# 1_P1_schdoc.net
KiCad netlist of a schematic drawn in Altium Designer
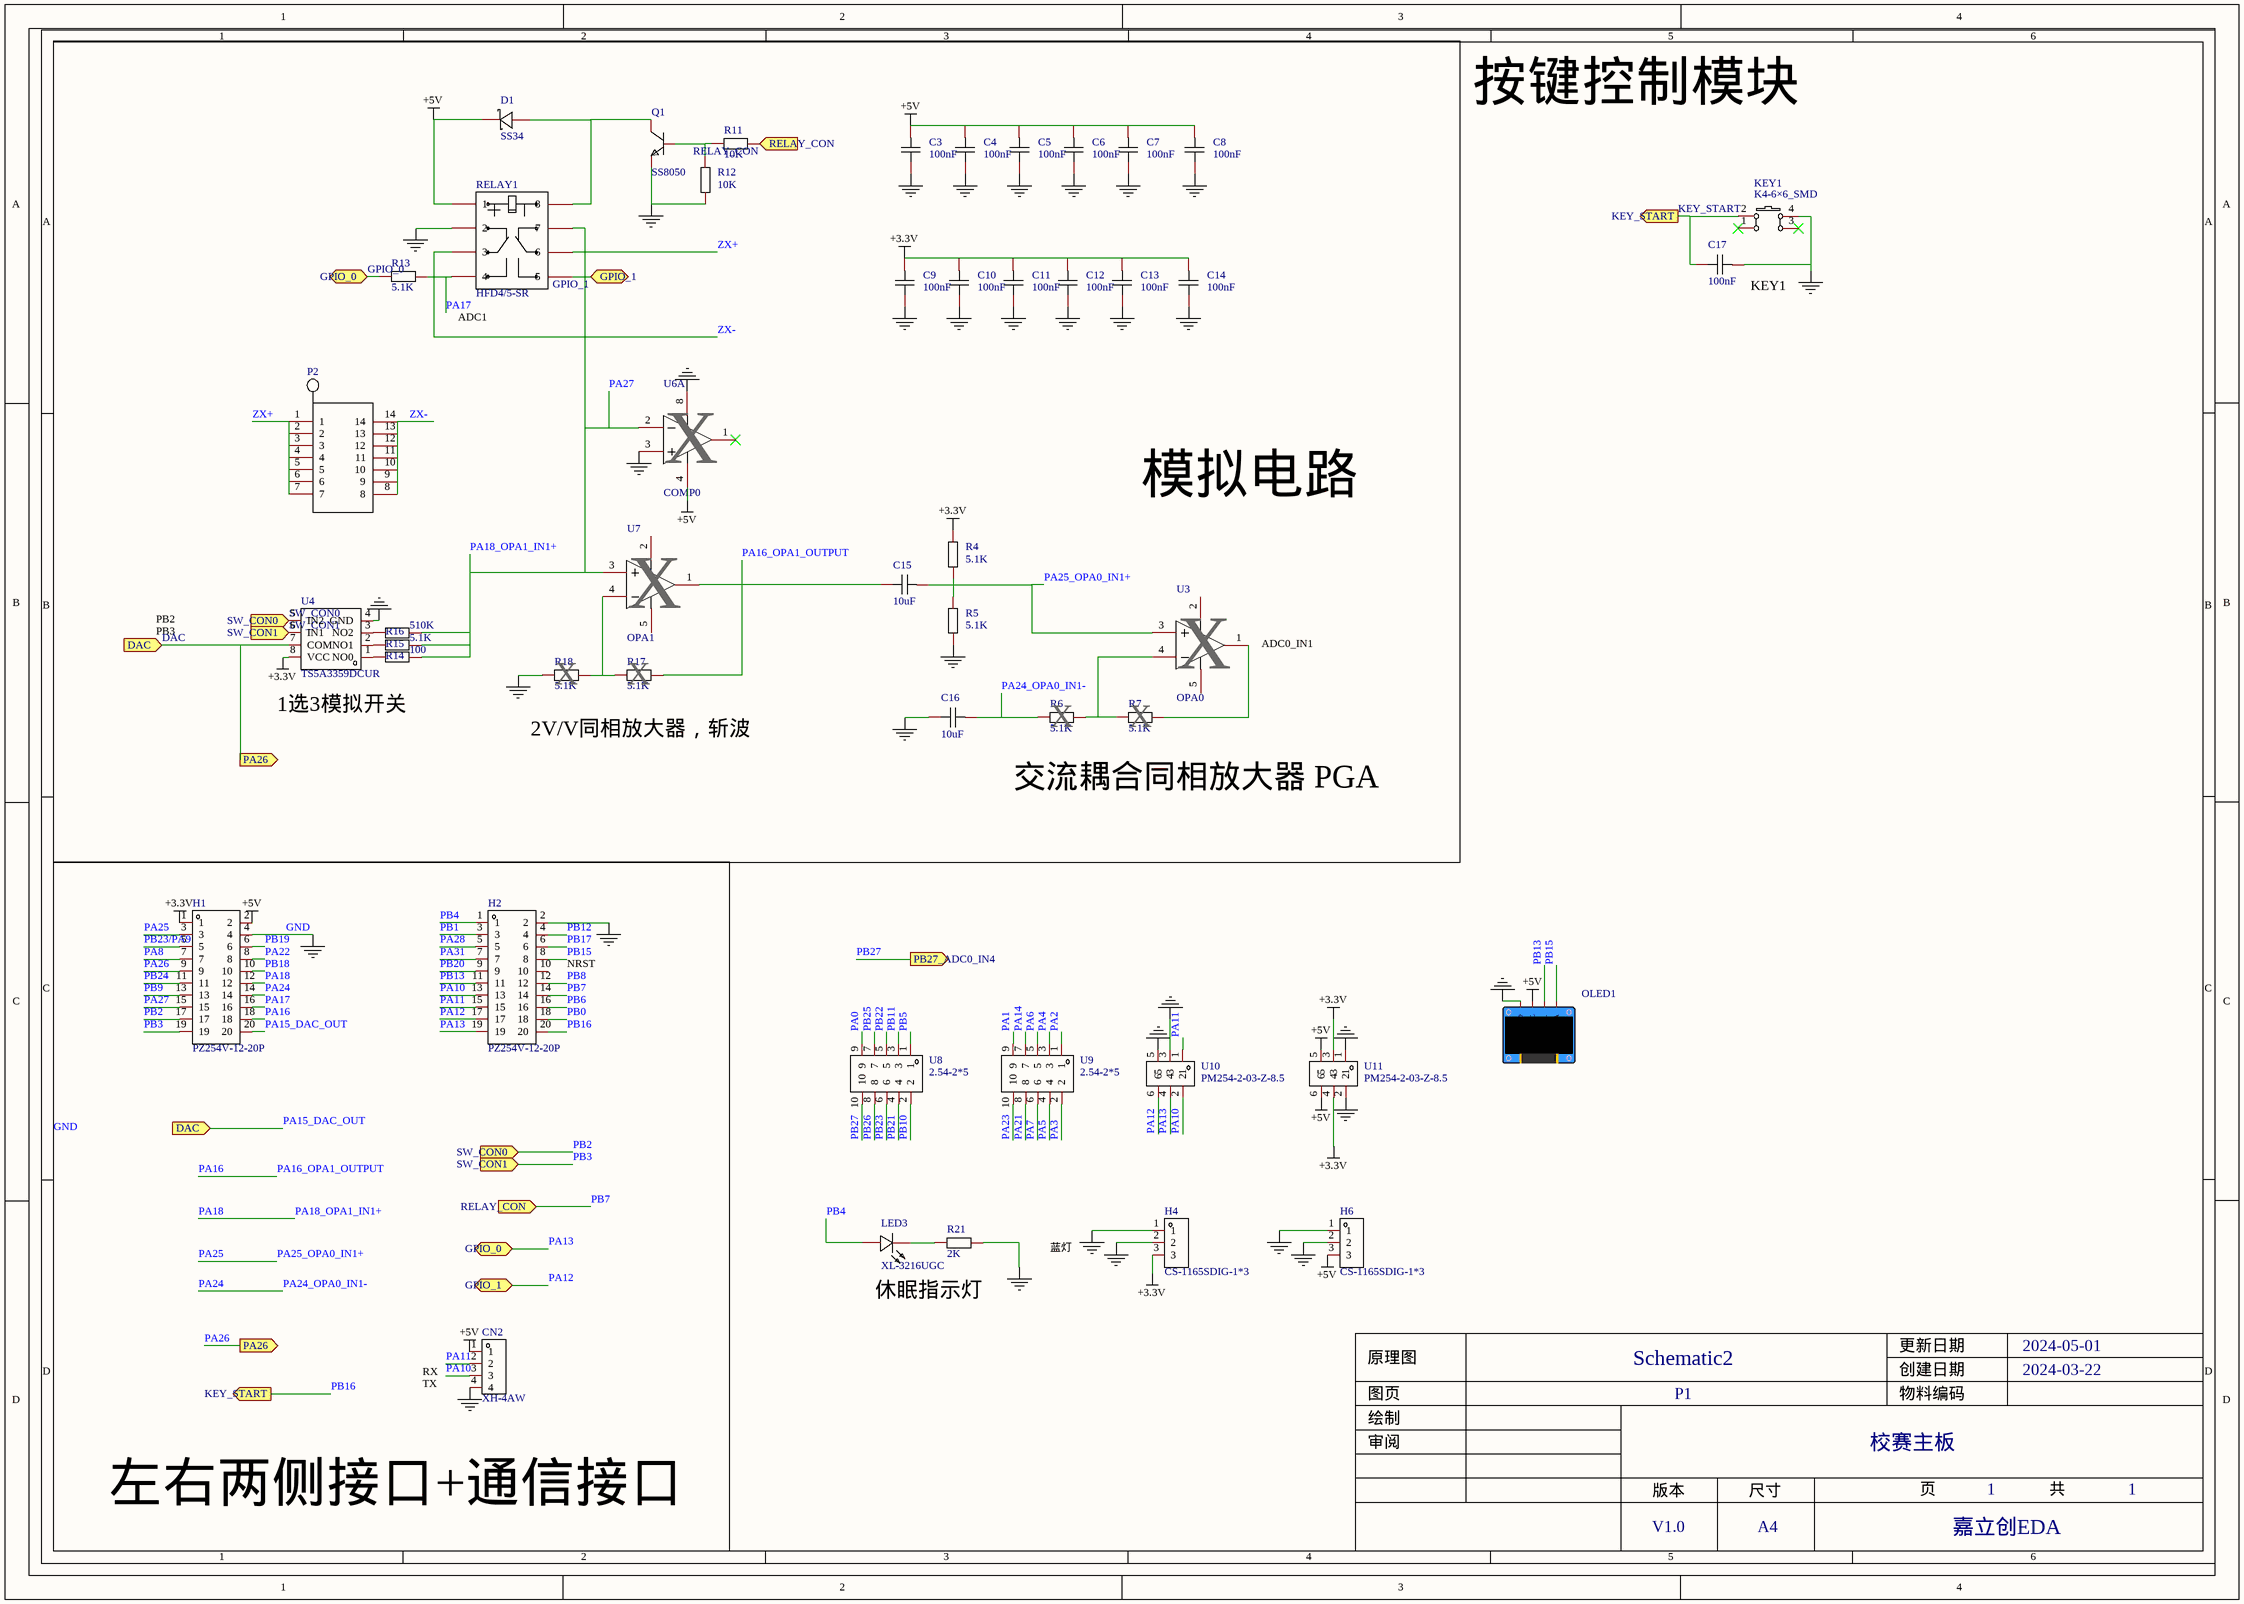
[diagram p0: 1_P1.schdoc.schdoc]

(export (version "E")
  (design (tool "Eeschema 10.0.6"))
  (components
    (comp (ref "C3")
      (value "100nF")
      (fields (field (name "NAME") "100nF"))
      (libsource (lib "altium-import") (part "root_1_CAP_0603_"))
    )
    (comp (ref "C4")
      (value "100nF")
      (fields (field (name "NAME") "100nF"))
      (libsource (lib "altium-import") (part "root_1_CAP_0603_"))
    )
    (comp (ref "C5")
      (value "100nF")
      (fields (field (name "NAME") "100nF"))
      (libsource (lib "altium-import") (part "root_1_CAP_0603_"))
    )
    (comp (ref "C6")
      (value "100nF")
      (fields (field (name "NAME") "100nF"))
      (libsource (lib "altium-import") (part "root_1_CAP_0603_"))
    )
    (comp (ref "C7")
      (value "100nF")
      (fields (field (name "NAME") "100nF"))
      (libsource (lib "altium-import") (part "root_1_CAP_0603_"))
    )
    (comp (ref "C8")
      (value "100nF")
      (fields (field (name "NAME") "100nF"))
      (libsource (lib "altium-import") (part "root_1_CAP_0603_"))
    )
    (comp (ref "C9")
      (value "100nF")
      (fields (field (name "NAME") "100nF"))
      (libsource (lib "altium-import") (part "root_1_CAP_0603_"))
    )
    (comp (ref "C10")
      (value "100nF")
      (fields (field (name "NAME") "100nF"))
      (libsource (lib "altium-import") (part "root_1_CAP_0603_"))
    )
    (comp (ref "C11")
      (value "100nF")
      (fields (field (name "NAME") "100nF"))
      (libsource (lib "altium-import") (part "root_1_CAP_0603_"))
    )
    (comp (ref "C12")
      (value "100nF")
      (fields (field (name "NAME") "100nF"))
      (libsource (lib "altium-import") (part "root_1_CAP_0603_"))
    )
    (comp (ref "C13")
      (value "100nF")
      (fields (field (name "NAME") "100nF"))
      (libsource (lib "altium-import") (part "root_1_CAP_0603_"))
    )
    (comp (ref "C14")
      (value "100nF")
      (fields (field (name "NAME") "100nF"))
      (libsource (lib "altium-import") (part "root_1_CAP_0603_"))
    )
    (comp (ref "C15")
      (value "10uF")
      (fields (field (name "NAME") "10uF"))
      (libsource (lib "altium-import") (part "root_0_CAP_0805_"))
    )
    (comp (ref "C16")
      (value "10uF")
      (fields (field (name "NAME") "10uF"))
      (libsource (lib "altium-import") (part "root_0_CAP_0805_"))
    )
    (comp (ref "C17")
      (value "100nF")
      (fields (field (name "NAME") "100nF"))
      (libsource (lib "altium-import") (part "root_0_CAP_0603_"))
    )
    (comp (ref "CN2")
      (value "XH-4AW")
      (fields (field (name "NAME") "XH-4AW") (field (name "MANUFACTURER") "HCTL(华灿天禄)"))
      (libsource (lib "altium-import") (part "root_0_XH-4AW_"))
    )
    (comp (ref "D1")
      (value "SS34")
      (description "二极管配置:独立式;正向压降(Vf):550mV@3A;直流反向耐压(Vr):40V;平均整流电流(Io):3A;")
      (fields (field (name "NAME") "SS34") (field (name "MANUFACTURER") "MDD"))
      (libsource (lib "altium-import") (part "root_0_SS34_C8678_"))
    )
    (comp (ref "H1")
      (value "PZ254V-12-20P")
      (fields (field (name "NAME") "PZ254V-12-20P") (field (name "MANUFACTURER") "XFCN(兴飞)"))
      (libsource (lib "altium-import") (part "root_0_PZ254V-12-20P_"))
    )
    (comp (ref "H2")
      (value "PZ254V-12-20P")
      (fields (field (name "NAME") "PZ254V-12-20P") (field (name "MANUFACTURER") "XFCN(兴飞)"))
      (libsource (lib "altium-import") (part "root_0_PZ254V-12-20P_"))
    )
    (comp (ref "H4")
      (value "CS-1165SDIG-1*3")
      (fields (field (name "NAME") "CS-1165SDIG-1*3") (field (name "MANUFACTURER") "CST(永丰盈)"))
      (libsource (lib "altium-import") (part "root_0_CS-1165SDIG-1*3_"))
    )
    (comp (ref "H6")
      (value "CS-1165SDIG-1*3")
      (fields (field (name "NAME") "CS-1165SDIG-1*3") (field (name "MANUFACTURER") "CST(永丰盈)"))
      (libsource (lib "altium-import") (part "root_0_CS-1165SDIG-1*3_"))
    )
    (comp (ref "KEY1")
      (value "K4-6×6_SMD")
      (fields
        (field (name "NAME") "K4-6×6_SMD")
        (field (name "MANUFACTURER") "韩国韩荣")
        (field (name "MANUFACTURER PART") "K2-6639SP-D4SC-04")
      )
      (libsource (lib "altium-import") (part "root_0_K4-6×6_SMD_"))
    )
    (comp (ref "LED3")
      (value "XL-3216UGC")
      (description "发光颜色:翠绿色;功率:80mW;正向电流:25mA;主波长:516nm~525nm;透镜颜色:无色透明透镜;色温:-;发光角度:120°;载带方式:正贴;工作温度:-30℃~+85℃;")
      (fields (field (name "NAME") "XL-3216UGC") (field (name "MANUFACTURER") "XINGLIGHT(成兴光)"))
      (libsource (lib "altium-import") (part "root_2_XL-3216UGC_"))
    )
    (comp (ref "OLED1")
      (value "0.96OLED模块_4P")
      (libsource (lib "altium-import") (part "root_0_0.96OLED模块_4P_"))
    )
    (comp (ref "P2")
      (value "IC锁紧座 14P 2.54mm")
      (libsource (lib "altium-import") (part "root_0_IC锁紧座 14P 2.54mm_"))
    )
    (comp (ref "Q1")
      (value "SS8050")
      (description "晶体管类型:NPN;集电极电流(Ic):1.5A;集射极击穿电压(Vceo):25V;功率(Pd):300mW;直流电流增益(hFE@Ic,Vce):200@100mA,1V;")
      (fields (field (name "NAME") "SS8050") (field (name "MANUFACTURER") "CJ(江苏长电/长晶)"))
      (libsource (lib "altium-import") (part "root_0_mirrored_SS8050_C2150_"))
    )
    (comp (ref "R4")
      (value "5.1K")
      (fields (field (name "NAME") "5.1K"))
      (libsource (lib "altium-import") (part "root_3_Res_0603_"))
    )
    (comp (ref "R5")
      (value "5.1K")
      (fields (field (name "NAME") "5.1K"))
      (libsource (lib "altium-import") (part "root_3_Res_0603_"))
    )
    (comp (ref "R6")
      (value "5.1K")
      (fields (field (name "NAME") "5.1K"))
      (libsource (lib "altium-import") (part "root_0_Res_0603_"))
    )
    (comp (ref "R7")
      (value "5.1K")
      (fields (field (name "NAME") "5.1K"))
      (libsource (lib "altium-import") (part "root_0_Res_0603_"))
    )
    (comp (ref "R11")
      (value "10K")
      (fields (field (name "NAME") "10K"))
      (libsource (lib "altium-import") (part "root_0_mirrored_Res_0603_"))
    )
    (comp (ref "R12")
      (value "10K")
      (fields (field (name "NAME") "10K"))
      (libsource (lib "altium-import") (part "root_1_mirrored_Res_0603_"))
    )
    (comp (ref "R13")
      (value "5.1K")
      (fields (field (name "NAME") "5.1K"))
      (libsource (lib "altium-import") (part "root_0_Res_0603_"))
    )
    (comp (ref "R14")
      (value "100")
      (fields (field (name "NAME") "100"))
      (libsource (lib "altium-import") (part "root_0_Res_0603_"))
    )
    (comp (ref "R15")
      (value "5.1K")
      (fields (field (name "NAME") "5.1K"))
      (libsource (lib "altium-import") (part "root_0_Res_0603_"))
    )
    (comp (ref "R16")
      (value "510K")
      (fields (field (name "NAME") "510K"))
      (libsource (lib "altium-import") (part "root_0_Res_0603_"))
    )
    (comp (ref "R17")
      (value "5.1K")
      (fields (field (name "NAME") "5.1K"))
      (libsource (lib "altium-import") (part "root_0_Res_0603_"))
    )
    (comp (ref "R18")
      (value "5.1K")
      (fields (field (name "NAME") "5.1K"))
      (libsource (lib "altium-import") (part "root_0_Res_0603_"))
    )
    (comp (ref "R21")
      (value "2K")
      (fields (field (name "NAME") "2K"))
      (libsource (lib "altium-import") (part "root_0_Res_0603_"))
    )
    (comp (ref "RELAY1")
      (value "HFD4/5-SR")
      (description "线圈电压:5V;触点形式:两组转换:2C(双刀双掷-转换);触点容量(电阻负载):1A@30VDC；300mA@125VAC;最大切换电压:250V@AC；220V@DC;最大切换电流:2A;")
      (fields (field (name "NAME") "HFD4/5-SR") (field (name "MANUFACTURER") "HF(宏发)"))
      (libsource (lib "altium-import") (part "root_3_HFD4/5-SR_"))
    )
    (comp (ref "U3")
      (value "OPA0")
      (description "放大器数:单路;增益带宽积(GBP):50MHz;输入偏置电流(Ib):0.2pA;压摆率(SR):25V/us;带宽(-3db):-;轨到轨:-;")
      (fields (field (name "NAME") "OPA0") (field (name "MANUFACTURER") "TI(德州仪器)"))
      (libsource (lib "altium-import") (part "root_2_mirrored_OPA365AIDBVR_"))
    )
    (comp (ref "U4")
      (value "TS5A3359DCUR")
      (description "开关电路:-;通道数:1;")
      (fields (field (name "NAME") "TS5A3359DCUR") (field (name "MANUFACTURER") "TI(德州仪器)"))
      (libsource (lib "altium-import") (part "root_2_TS5A3359DCUR_"))
    )
    (comp (ref "U6")
      (value "COMP0")
      (fields (field (name "NAME") "COMP0") (field (name "MANUFACTURER") "HGSEMI(华冠)"))
      (libsource (lib "altium-import") (part "root_0_LM393M/TR_"))
    )
    (comp (ref "U7")
      (value "OPA1")
      (description "放大器数:单路;增益带宽积(GBP):50MHz;输入偏置电流(Ib):0.2pA;压摆率(SR):25V/us;带宽(-3db):-;轨到轨:-;")
      (fields (field (name "NAME") "OPA1") (field (name "MANUFACTURER") "TI(德州仪器)"))
      (libsource (lib "altium-import") (part "root_2_mirrored_OPA365AIDBVR_"))
    )
    (comp (ref "U8")
      (value "2.54-2*5")
      (fields (field (name "NAME") "2.54-2*5") (field (name "MANUFACTURER") "ZHOURI(洲日)"))
      (libsource (lib "altium-import") (part "root_3_2.54-2*5_"))
    )
    (comp (ref "U9")
      (value "2.54-2*5")
      (fields (field (name "NAME") "2.54-2*5") (field (name "MANUFACTURER") "ZHOURI(洲日)"))
      (libsource (lib "altium-import") (part "root_3_2.54-2*5_"))
    )
    (comp (ref "U10")
      (value "PM254-2-03-Z-8.5")
      (fields (field (name "NAME") "PM254-2-03-Z-8.5") (field (name "MANUFACTURER") "HCTL(华灿天禄)"))
      (libsource (lib "altium-import") (part "root_3_PM254-2-03-Z-8.5_"))
    )
    (comp (ref "U11")
      (value "PM254-2-03-Z-8.5")
      (fields (field (name "NAME") "PM254-2-03-Z-8.5") (field (name "MANUFACTURER") "HCTL(华灿天禄)"))
      (libsource (lib "altium-import") (part "root_3_PM254-2-03-Z-8.5_"))
    )
  )
  (nets
    (net (code "1") (name "+3.3V") (class "Default")
      (node (ref "C10") (pin "2") (pinfunction "2_2") (pintype "passive"))
      (node (ref "C11") (pin "2") (pinfunction "2_2") (pintype "passive"))
      (node (ref "C12") (pin "2") (pinfunction "2_2") (pintype "passive"))
      (node (ref "C13") (pin "2") (pinfunction "2_2") (pintype "passive"))
      (node (ref "C14") (pin "2") (pinfunction "2_2") (pintype "passive"))
      (node (ref "C9") (pin "2") (pinfunction "2_2") (pintype "passive"))
      (node (ref "H1") (pin "1") (pinfunction "1_1") (pintype "passive"))
      (node (ref "H4") (pin "3") (pinfunction "3_3") (pintype "passive"))
      (node (ref "R4") (pin "1") (pinfunction "1_1") (pintype "passive"))
      (node (ref "U11") (pin "3") (pinfunction "3_3") (pintype "passive"))
      (node (ref "U11") (pin "4") (pinfunction "4_4") (pintype "passive"))
      (node (ref "U4") (pin "8") (pinfunction "VCC_8") (pintype "passive"))
    )
    (net (code "2") (name "+5V") (class "Default")
      (node (ref "C3") (pin "2") (pinfunction "2_2") (pintype "passive"))
      (node (ref "C4") (pin "2") (pinfunction "2_2") (pintype "passive"))
      (node (ref "C5") (pin "2") (pinfunction "2_2") (pintype "passive"))
      (node (ref "C6") (pin "2") (pinfunction "2_2") (pintype "passive"))
      (node (ref "C7") (pin "2") (pinfunction "2_2") (pintype "passive"))
      (node (ref "C8") (pin "2") (pinfunction "2_2") (pintype "passive"))
      (node (ref "CN2") (pin "1") (pinfunction "1_1") (pintype "passive"))
      (node (ref "D1") (pin "1") (pinfunction "K_1") (pintype "passive"))
      (node (ref "H1") (pin "2") (pinfunction "2_2") (pintype "passive"))
      (node (ref "H6") (pin "3") (pinfunction "3_3") (pintype "passive"))
      (node (ref "OLED1") (pin "2") (pinfunction "VCC_2") (pintype "passive"))
      (node (ref "RELAY1") (pin "1") (pinfunction "1_1") (pintype "passive"))
      (node (ref "U11") (pin "5") (pinfunction "5_5") (pintype "passive"))
      (node (ref "U11") (pin "6") (pinfunction "6_6") (pintype "passive"))
      (node (ref "U6") (pin "4") (pinfunction "GND_4") (pintype "passive"))
    )
    (net (code "3") (name "/DAC") (class "Default")
      (node (ref "H1") (pin "20") (pinfunction "20_20") (pintype "passive"))
      (node (ref "H1") (pin "9") (pinfunction "9_9") (pintype "passive"))
      (node (ref "U4") (pin "7") (pinfunction "COM_7") (pintype "passive"))
    )
    (net (code "4") (name "/GND") (class "Default")
      (node (ref "C10") (pin "1") (pinfunction "1_1") (pintype "passive"))
      (node (ref "C11") (pin "1") (pinfunction "1_1") (pintype "passive"))
      (node (ref "C12") (pin "1") (pinfunction "1_1") (pintype "passive"))
      (node (ref "C13") (pin "1") (pinfunction "1_1") (pintype "passive"))
      (node (ref "C14") (pin "1") (pinfunction "1_1") (pintype "passive"))
      (node (ref "C16") (pin "1") (pinfunction "1_1") (pintype "passive"))
      (node (ref "C17") (pin "2") (pinfunction "2_2") (pintype "passive"))
      (node (ref "C3") (pin "1") (pinfunction "1_1") (pintype "passive"))
      (node (ref "C4") (pin "1") (pinfunction "1_1") (pintype "passive"))
      (node (ref "C5") (pin "1") (pinfunction "1_1") (pintype "passive"))
      (node (ref "C6") (pin "1") (pinfunction "1_1") (pintype "passive"))
      (node (ref "C7") (pin "1") (pinfunction "1_1") (pintype "passive"))
      (node (ref "C8") (pin "1") (pinfunction "1_1") (pintype "passive"))
      (node (ref "C9") (pin "1") (pinfunction "1_1") (pintype "passive"))
      (node (ref "CN2") (pin "4") (pinfunction "4_4") (pintype "passive"))
      (node (ref "H1") (pin "4") (pinfunction "4_4") (pintype "passive"))
      (node (ref "H2") (pin "2") (pinfunction "2_2") (pintype "passive"))
      (node (ref "H4") (pin "1") (pinfunction "1_1") (pintype "passive"))
      (node (ref "H4") (pin "2") (pinfunction "2_2") (pintype "passive"))
      (node (ref "H6") (pin "1") (pinfunction "1_1") (pintype "passive"))
      (node (ref "H6") (pin "2") (pinfunction "2_2") (pintype "passive"))
      (node (ref "KEY1") (pin "4") (pinfunction "4_4") (pintype "passive"))
      (node (ref "OLED1") (pin "1") (pinfunction "GND_1") (pintype "passive"))
      (node (ref "Q1") (pin "2") (pinfunction "E_2") (pintype "passive"))
      (node (ref "R12") (pin "1") (pinfunction "1_1") (pintype "passive"))
      (node (ref "R18") (pin "1") (pinfunction "1_1") (pintype "passive"))
      (node (ref "R21") (pin "2") (pinfunction "2_2") (pintype "passive"))
      (node (ref "R5") (pin "2") (pinfunction "2_2") (pintype "passive"))
      (node (ref "RELAY1") (pin "2") (pinfunction "2_2") (pintype "passive"))
      (node (ref "U10") (pin "3") (pinfunction "3_3") (pintype "passive"))
      (node (ref "U10") (pin "5") (pinfunction "5_5") (pintype "passive"))
      (node (ref "U11") (pin "1") (pinfunction "1_1") (pintype "passive"))
      (node (ref "U11") (pin "2") (pinfunction "2_2") (pintype "passive"))
      (node (ref "U4") (pin "4") (pinfunction "GND_4") (pintype "passive"))
      (node (ref "U6") (pin "3") (pinfunction "IN1+_3") (pintype "passive"))
      (node (ref "U6") (pin "8") (pinfunction "VCC_8") (pintype "passive"))
    )
    (net (code "5") (name "/GPIO_0") (class "Default")
      (node (ref "H2") (pin "19") (pinfunction "19_19") (pintype "passive"))
      (node (ref "R13") (pin "1") (pinfunction "1_1") (pintype "passive"))
      (node (ref "U10") (pin "4") (pinfunction "4_4") (pintype "passive"))
    )
    (net (code "6") (name "/GPIO_1") (class "Default")
      (node (ref "H2") (pin "17") (pinfunction "17_17") (pintype "passive"))
      (node (ref "RELAY1") (pin "5") (pinfunction "5_5") (pintype "passive"))
      (node (ref "U10") (pin "6") (pinfunction "6_6") (pintype "passive"))
    )
    (net (code "7") (name "/KEY_START") (class "Default")
      (node (ref "C17") (pin "1") (pinfunction "1_1") (pintype "passive"))
      (node (ref "H2") (pin "20") (pinfunction "20_20") (pintype "passive"))
      (node (ref "KEY1") (pin "2") (pinfunction "2_2") (pintype "passive"))
    )
    (net (code "8") (name "/PA0") (class "Default")
      (node (ref "U8") (pin "9") (pinfunction "9_9") (pintype "passive"))
    )
    (net (code "9") (name "/PA1") (class "Default")
      (node (ref "U9") (pin "9") (pinfunction "9_9") (pintype "passive"))
    )
    (net (code "10") (name "/PA2") (class "Default")
      (node (ref "U9") (pin "1") (pinfunction "1_1") (pintype "passive"))
    )
    (net (code "11") (name "/PA3") (class "Default")
      (node (ref "U9") (pin "2") (pinfunction "2_2") (pintype "passive"))
    )
    (net (code "12") (name "/PA4") (class "Default")
      (node (ref "U9") (pin "3") (pinfunction "3_3") (pintype "passive"))
    )
    (net (code "13") (name "/PA5") (class "Default")
      (node (ref "U9") (pin "4") (pinfunction "4_4") (pintype "passive"))
    )
    (net (code "14") (name "/PA6") (class "Default")
      (node (ref "U9") (pin "5") (pinfunction "5_5") (pintype "passive"))
    )
    (net (code "15") (name "/PA7") (class "Default")
      (node (ref "U9") (pin "6") (pinfunction "6_6") (pintype "passive"))
    )
    (net (code "16") (name "/PA8") (class "Default")
      (node (ref "H1") (pin "7") (pinfunction "7_7") (pintype "passive"))
    )
    (net (code "17") (name "/PA10") (class "Default")
      (node (ref "CN2") (pin "3") (pinfunction "3_3") (pintype "passive"))
      (node (ref "H2") (pin "13") (pinfunction "13_13") (pintype "passive"))
      (node (ref "U10") (pin "2") (pinfunction "2_2") (pintype "passive"))
    )
    (net (code "18") (name "/PA11") (class "Default")
      (node (ref "CN2") (pin "2") (pinfunction "2_2") (pintype "passive"))
      (node (ref "H2") (pin "15") (pinfunction "15_15") (pintype "passive"))
      (node (ref "U10") (pin "1") (pinfunction "1_1") (pintype "passive"))
    )
    (net (code "19") (name "/PA14") (class "Default")
      (node (ref "U9") (pin "7") (pinfunction "7_7") (pintype "passive"))
    )
    (net (code "20") (name "/PA16") (class "Default")
      (node (ref "C15") (pin "1") (pinfunction "1_1") (pintype "passive"))
      (node (ref "H1") (pin "18") (pinfunction "18_18") (pintype "passive"))
      (node (ref "R17") (pin "2") (pinfunction "2_2") (pintype "passive"))
      (node (ref "U7") (pin "1") (pinfunction "OUT_1") (pintype "passive"))
    )
    (net (code "21") (name "/PA17") (class "Default")
      (node (ref "H1") (pin "16") (pinfunction "16_16") (pintype "passive"))
      (node (ref "R13") (pin "2") (pinfunction "2_2") (pintype "passive"))
      (node (ref "RELAY1") (pin "4") (pinfunction "4_4") (pintype "passive"))
    )
    (net (code "22") (name "/PA18") (class "Default")
      (node (ref "H1") (pin "12") (pinfunction "12_12") (pintype "passive"))
      (node (ref "H1") (pin "15") (pinfunction "15_15") (pintype "passive"))
      (node (ref "R14") (pin "2") (pinfunction "2_2") (pintype "passive"))
      (node (ref "R15") (pin "2") (pinfunction "2_2") (pintype "passive"))
      (node (ref "R16") (pin "2") (pinfunction "2_2") (pintype "passive"))
      (node (ref "RELAY1") (pin "7") (pinfunction "7_7") (pintype "passive"))
      (node (ref "U6") (pin "2") (pinfunction "IN1-_2") (pintype "passive"))
      (node (ref "U7") (pin "3") (pinfunction "IN+_3") (pintype "passive"))
    )
    (net (code "23") (name "/PA21") (class "Default")
      (node (ref "U9") (pin "8") (pinfunction "8_8") (pintype "passive"))
    )
    (net (code "24") (name "/PA22") (class "Default")
      (node (ref "H1") (pin "8") (pinfunction "8_8") (pintype "passive"))
    )
    (net (code "25") (name "/PA23") (class "Default")
      (node (ref "U9") (pin "10") (pinfunction "10_10") (pintype "passive"))
    )
    (net (code "26") (name "/PA24") (class "Default")
      (node (ref "C16") (pin "2") (pinfunction "2_2") (pintype "passive"))
      (node (ref "H1") (pin "14") (pinfunction "14_14") (pintype "passive"))
      (node (ref "R6") (pin "1") (pinfunction "1_1") (pintype "passive"))
    )
    (net (code "27") (name "/PA25") (class "Default")
      (node (ref "C15") (pin "2") (pinfunction "2_2") (pintype "passive"))
      (node (ref "H1") (pin "3") (pinfunction "3_3") (pintype "passive"))
      (node (ref "R4") (pin "2") (pinfunction "2_2") (pintype "passive"))
      (node (ref "R5") (pin "1") (pinfunction "1_1") (pintype "passive"))
      (node (ref "U3") (pin "3") (pinfunction "IN+_3") (pintype "passive"))
    )
    (net (code "28") (name "/PA28") (class "Default")
      (node (ref "H2") (pin "5") (pinfunction "5_5") (pintype "passive"))
    )
    (net (code "29") (name "/PA31") (class "Default")
      (node (ref "H2") (pin "7") (pinfunction "7_7") (pintype "passive"))
    )
    (net (code "30") (name "/PB0") (class "Default")
      (node (ref "H2") (pin "18") (pinfunction "18_18") (pintype "passive"))
    )
    (net (code "31") (name "/PB1") (class "Default")
      (node (ref "H2") (pin "3") (pinfunction "3_3") (pintype "passive"))
    )
    (net (code "32") (name "/PB2") (class "Default")
      (node (ref "H1") (pin "17") (pinfunction "17_17") (pintype "passive"))
      (node (ref "U4") (pin "5") (pinfunction "IN2_5") (pintype "passive"))
    )
    (net (code "33") (name "/PB3") (class "Default")
      (node (ref "H1") (pin "19") (pinfunction "19_19") (pintype "passive"))
      (node (ref "U4") (pin "6") (pinfunction "IN1_6") (pintype "passive"))
    )
    (net (code "34") (name "/PB4") (class "Default")
      (node (ref "H2") (pin "1") (pinfunction "1_1") (pintype "passive"))
      (node (ref "LED3") (pin "1") (pinfunction "A_1") (pintype "passive"))
    )
    (net (code "35") (name "/PB5") (class "Default")
      (node (ref "U8") (pin "1") (pinfunction "1_1") (pintype "passive"))
    )
    (net (code "36") (name "/PB6") (class "Default")
      (node (ref "H2") (pin "16") (pinfunction "16_16") (pintype "passive"))
    )
    (net (code "37") (name "/PB7") (class "Default")
      (node (ref "H2") (pin "14") (pinfunction "14_14") (pintype "passive"))
      (node (ref "R11") (pin "1") (pinfunction "1_1") (pintype "passive"))
    )
    (net (code "38") (name "/PB8") (class "Default")
      (node (ref "H2") (pin "12") (pinfunction "12_12") (pintype "passive"))
    )
    (net (code "39") (name "/PB9") (class "Default")
      (node (ref "H1") (pin "13") (pinfunction "13_13") (pintype "passive"))
    )
    (net (code "40") (name "/PB10") (class "Default")
      (node (ref "U8") (pin "2") (pinfunction "2_2") (pintype "passive"))
    )
    (net (code "41") (name "/PB11") (class "Default")
      (node (ref "U8") (pin "3") (pinfunction "3_3") (pintype "passive"))
    )
    (net (code "42") (name "/PB12") (class "Default")
      (node (ref "H2") (pin "4") (pinfunction "4_4") (pintype "passive"))
    )
    (net (code "43") (name "/PB13") (class "Default")
      (node (ref "H2") (pin "11") (pinfunction "11_11") (pintype "passive"))
      (node (ref "OLED1") (pin "3") (pinfunction "SCL_3") (pintype "passive"))
    )
    (net (code "44") (name "/PB15") (class "Default")
      (node (ref "H2") (pin "8") (pinfunction "8_8") (pintype "passive"))
      (node (ref "OLED1") (pin "4") (pinfunction "SDA_4") (pintype "passive"))
    )
    (net (code "45") (name "/PB17") (class "Default")
      (node (ref "H2") (pin "6") (pinfunction "6_6") (pintype "passive"))
    )
    (net (code "46") (name "/PB18") (class "Default")
      (node (ref "H1") (pin "10") (pinfunction "10_10") (pintype "passive"))
    )
    (net (code "47") (name "/PB19") (class "Default")
      (node (ref "H1") (pin "6") (pinfunction "6_6") (pintype "passive"))
    )
    (net (code "48") (name "/PB20") (class "Default")
      (node (ref "H2") (pin "9") (pinfunction "9_9") (pintype "passive"))
    )
    (net (code "49") (name "/PB21") (class "Default")
      (node (ref "U8") (pin "4") (pinfunction "4_4") (pintype "passive"))
    )
    (net (code "50") (name "/PB22") (class "Default")
      (node (ref "U8") (pin "5") (pinfunction "5_5") (pintype "passive"))
    )
    (net (code "51") (name "/PB23") (class "Default")
      (node (ref "U8") (pin "6") (pinfunction "6_6") (pintype "passive"))
    )
    (net (code "52") (name "/PB23{slash}PA9") (class "Default")
      (node (ref "H1") (pin "5") (pinfunction "5_5") (pintype "passive"))
    )
    (net (code "53") (name "/PB24") (class "Default")
      (node (ref "H1") (pin "11") (pinfunction "11_11") (pintype "passive"))
    )
    (net (code "54") (name "/PB25") (class "Default")
      (node (ref "U8") (pin "7") (pinfunction "7_7") (pintype "passive"))
    )
    (net (code "55") (name "/PB26") (class "Default")
      (node (ref "U8") (pin "8") (pinfunction "8_8") (pintype "passive"))
    )
    (net (code "56") (name "/PB27") (class "Default")
      (node (ref "U8") (pin "10") (pinfunction "10_10") (pintype "passive"))
    )
    (net (code "57") (name "/ZX+") (class "Default")
      (node (ref "P2") (pin "1") (pinfunction "1_1") (pintype "passive"))
      (node (ref "P2") (pin "2") (pinfunction "2_2") (pintype "passive"))
      (node (ref "P2") (pin "3") (pinfunction "3_3") (pintype "passive"))
      (node (ref "P2") (pin "4") (pinfunction "4_4") (pintype "passive"))
      (node (ref "P2") (pin "5") (pinfunction "5_5") (pintype "passive"))
      (node (ref "P2") (pin "6") (pinfunction "6_6") (pintype "passive"))
      (node (ref "P2") (pin "7") (pinfunction "7_7") (pintype "passive"))
      (node (ref "RELAY1") (pin "6") (pinfunction "6_6") (pintype "passive"))
    )
    (net (code "58") (name "/ZX-") (class "Default")
      (node (ref "P2") (pin "10") (pinfunction "10_10") (pintype "passive"))
      (node (ref "P2") (pin "11") (pinfunction "11_11") (pintype "passive"))
      (node (ref "P2") (pin "12") (pinfunction "12_12") (pintype "passive"))
      (node (ref "P2") (pin "13") (pinfunction "13_13") (pintype "passive"))
      (node (ref "P2") (pin "14") (pinfunction "14_14") (pintype "passive"))
      (node (ref "P2") (pin "8") (pinfunction "8_8") (pintype "passive"))
      (node (ref "P2") (pin "9") (pinfunction "9_9") (pintype "passive"))
      (node (ref "RELAY1") (pin "3") (pinfunction "3_3") (pintype "passive"))
    )
    (net (code "59") (name "Net-(D1-A)") (class "Default")
      (node (ref "D1") (pin "2") (pinfunction "A_2") (pintype "passive"))
      (node (ref "Q1") (pin "3") (pinfunction "C_3") (pintype "passive"))
      (node (ref "RELAY1") (pin "8") (pinfunction "8_8") (pintype "passive"))
    )
    (net (code "60") (name "Net-(LED3-K)") (class "Default")
      (node (ref "LED3") (pin "2") (pinfunction "K_2") (pintype "passive"))
      (node (ref "R21") (pin "1") (pinfunction "1_1") (pintype "passive"))
    )
    (net (code "61") (name "Net-(Q1-B)") (class "Default")
      (node (ref "Q1") (pin "1") (pinfunction "B_1") (pintype "passive"))
      (node (ref "R11") (pin "2") (pinfunction "2_2") (pintype "passive"))
      (node (ref "R12") (pin "2") (pinfunction "2_2") (pintype "passive"))
    )
    (net (code "62") (name "Net-(U3-IN-)") (class "Default")
      (node (ref "R6") (pin "2") (pinfunction "2_2") (pintype "passive"))
      (node (ref "R7") (pin "1") (pinfunction "1_1") (pintype "passive"))
      (node (ref "U3") (pin "4") (pinfunction "IN-_4") (pintype "passive"))
    )
    (net (code "63") (name "Net-(U3-OUT)") (class "Default")
      (node (ref "R7") (pin "2") (pinfunction "2_2") (pintype "passive"))
      (node (ref "U3") (pin "1") (pinfunction "OUT_1") (pintype "passive"))
    )
    (net (code "64") (name "Net-(U4-NO0)") (class "Default")
      (node (ref "R14") (pin "1") (pinfunction "1_1") (pintype "passive"))
      (node (ref "U4") (pin "1") (pinfunction "NO0_1") (pintype "passive"))
    )
    (net (code "65") (name "Net-(U4-NO1)") (class "Default")
      (node (ref "R15") (pin "1") (pinfunction "1_1") (pintype "passive"))
      (node (ref "U4") (pin "2") (pinfunction "NO1_2") (pintype "passive"))
    )
    (net (code "66") (name "Net-(U4-NO2)") (class "Default")
      (node (ref "R16") (pin "1") (pinfunction "1_1") (pintype "passive"))
      (node (ref "U4") (pin "3") (pinfunction "NO2_3") (pintype "passive"))
    )
    (net (code "67") (name "Net-(U7-IN-)") (class "Default")
      (node (ref "R17") (pin "1") (pinfunction "1_1") (pintype "passive"))
      (node (ref "R18") (pin "2") (pinfunction "2_2") (pintype "passive"))
      (node (ref "U7") (pin "4") (pinfunction "IN-_4") (pintype "passive"))
    )
    (net (code "68") (name "unconnected-(H2-Pad10)") (class "Default")
      (node (ref "H2") (pin "10") (pinfunction "10_10") (pintype "passive"))
    )
    (net (code "69") (name "unconnected-(KEY1-Pad1)") (class "Default")
      (node (ref "KEY1") (pin "1") (pinfunction "1_1") (pintype "passive+no_connect"))
    )
    (net (code "70") (name "unconnected-(KEY1-Pad3)") (class "Default")
      (node (ref "KEY1") (pin "3") (pinfunction "3_3") (pintype "passive+no_connect"))
    )
    (net (code "71") (name "unconnected-(U3-VS+-Pad5)") (class "Default")
      (node (ref "U3") (pin "5") (pinfunction "VS+_5") (pintype "passive"))
    )
    (net (code "72") (name "unconnected-(U3-VS--Pad2)") (class "Default")
      (node (ref "U3") (pin "2") (pinfunction "VS-_2") (pintype "passive"))
    )
    (net (code "73") (name "unconnected-(U6A-OUT1-Pad1)") (class "Default")
      (node (ref "U6") (pin "1") (pinfunction "OUT1_1") (pintype "passive+no_connect"))
    )
    (net (code "74") (name "unconnected-(U7-VS+-Pad5)") (class "Default")
      (node (ref "U7") (pin "5") (pinfunction "VS+_5") (pintype "passive"))
    )
    (net (code "75") (name "unconnected-(U7-VS--Pad2)") (class "Default")
      (node (ref "U7") (pin "2") (pinfunction "VS-_2") (pintype "passive"))
    )
  )
)
